# analog-frontend.net
KiCad netlist of a schematic drawn in EAGLE
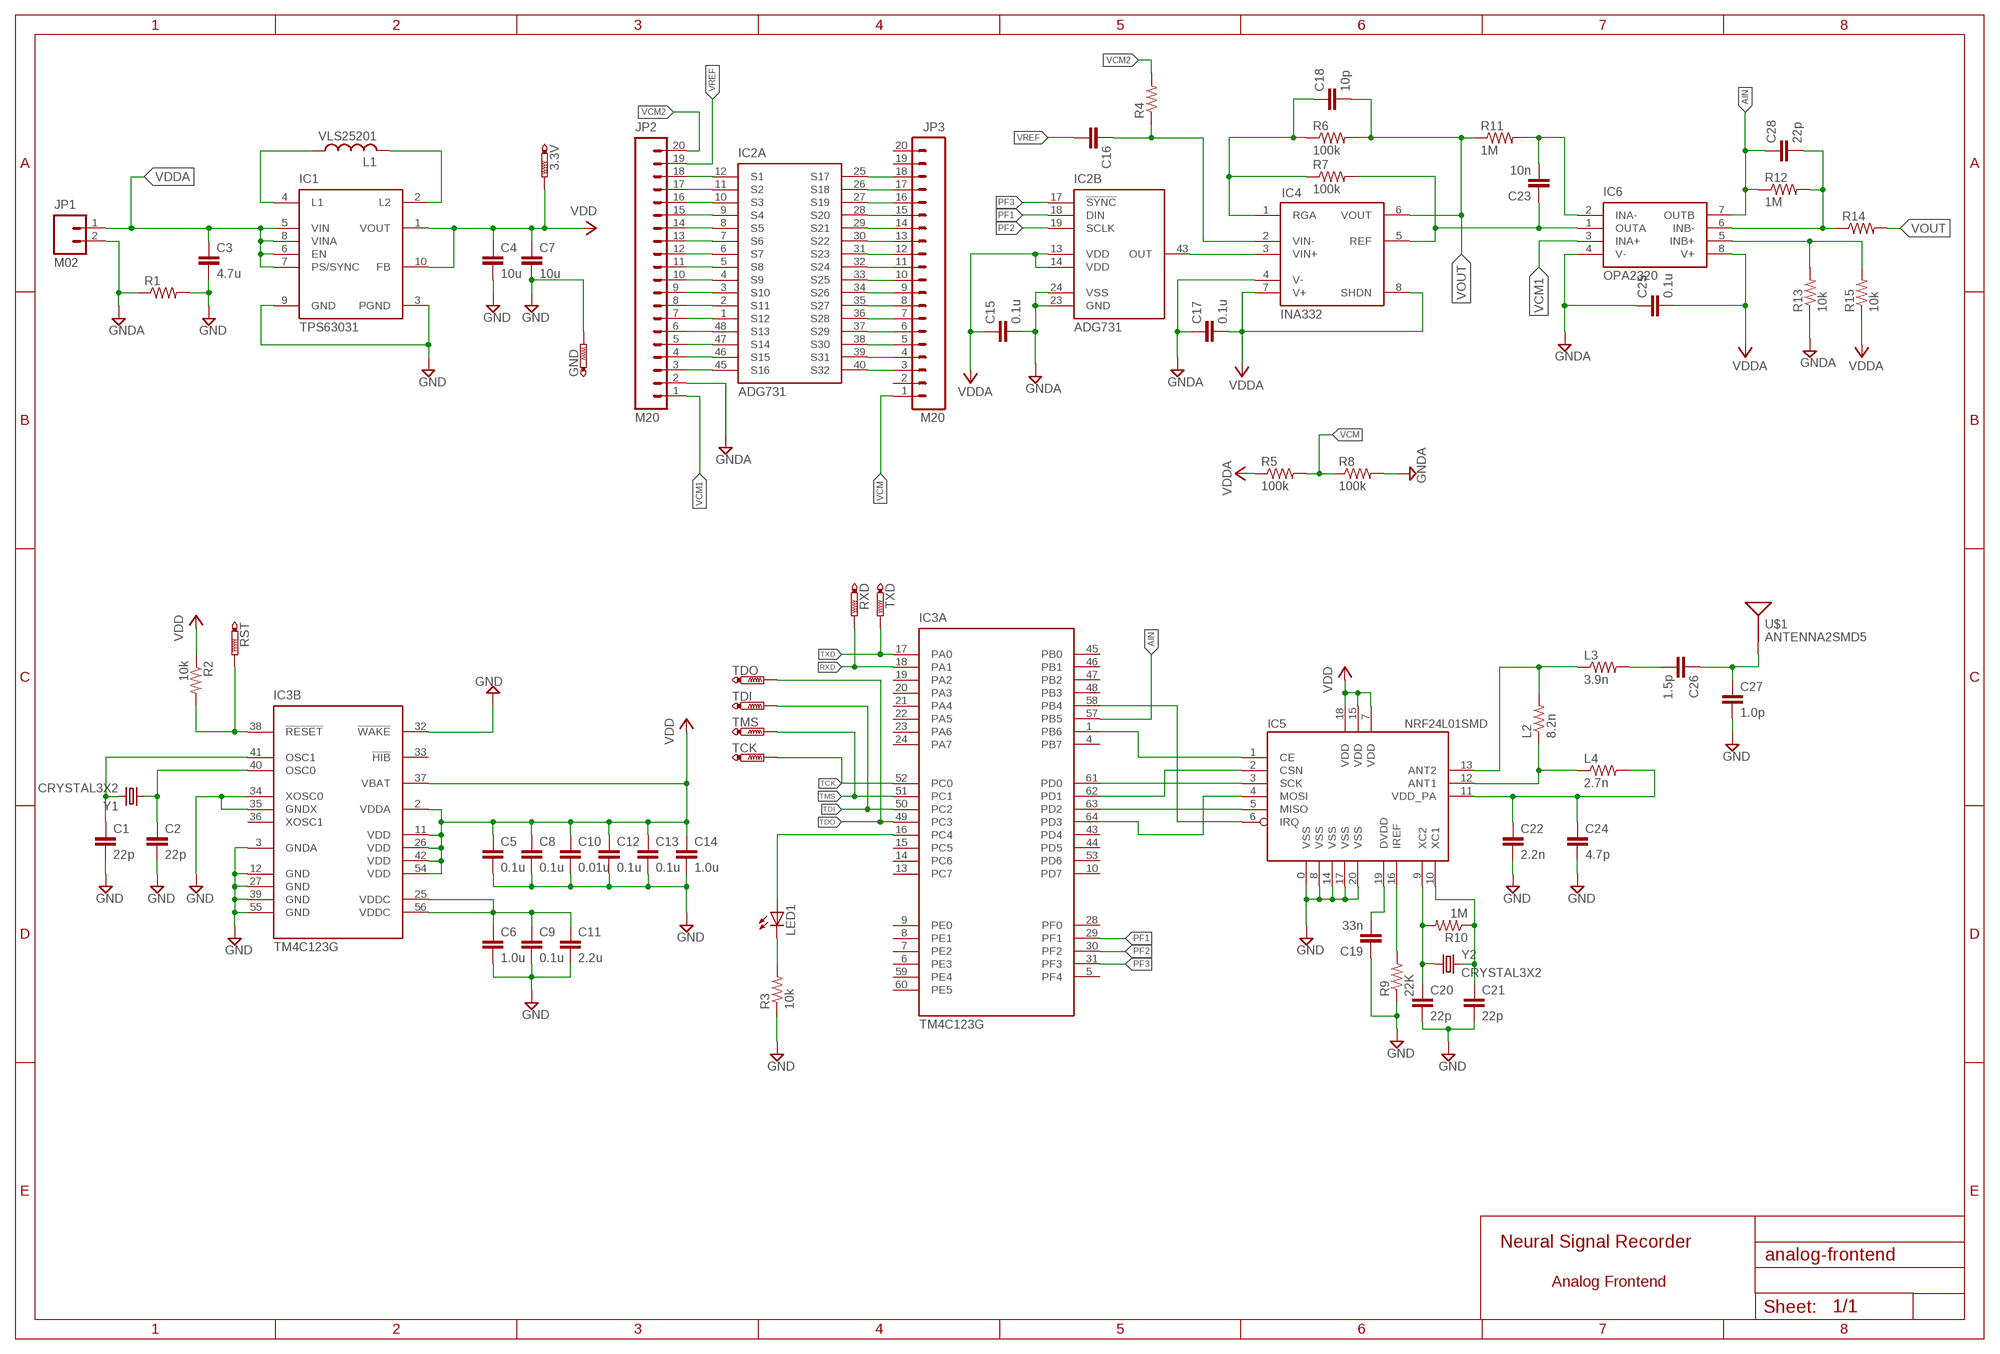
[diagram p0: schematic, sheet 1]

(export (version "E")
  (design (tool "Eeschema 10.0.6"))
  (components
    (comp (ref "3.3V")
      (value "PTR1B1,27")
      (footprint "eagle-import:B1,27")
      (libsource (lib "eagle-import") (part "PTR1B1,27"))
    )
    (comp (ref "C1")
      (value "22p")
      (footprint "eagle-import:C0402")
      (libsource (lib "eagle-import") (part "C-EUC0402"))
    )
    (comp (ref "C2")
      (value "22p")
      (footprint "eagle-import:C0402")
      (libsource (lib "eagle-import") (part "C-EUC0402"))
    )
    (comp (ref "C3")
      (value "4.7u")
      (footprint "eagle-import:C0402")
      (libsource (lib "eagle-import") (part "C-EUC0402"))
    )
    (comp (ref "C4")
      (value "10u")
      (footprint "eagle-import:C0402")
      (libsource (lib "eagle-import") (part "C-EUC0402"))
    )
    (comp (ref "C5")
      (value "0.1u")
      (footprint "eagle-import:C0402")
      (libsource (lib "eagle-import") (part "C-EUC0402"))
    )
    (comp (ref "C6")
      (value "1.0u")
      (footprint "eagle-import:C0402")
      (libsource (lib "eagle-import") (part "C-EUC0402"))
    )
    (comp (ref "C7")
      (value "10u")
      (footprint "eagle-import:C0402")
      (libsource (lib "eagle-import") (part "C-EUC0402"))
    )
    (comp (ref "C8")
      (value "0.1u")
      (footprint "eagle-import:C0402")
      (libsource (lib "eagle-import") (part "C-EUC0402"))
    )
    (comp (ref "C9")
      (value "0.1u")
      (footprint "eagle-import:C0402")
      (libsource (lib "eagle-import") (part "C-EUC0402"))
    )
    (comp (ref "C10")
      (value "0.01u")
      (footprint "eagle-import:C0402")
      (libsource (lib "eagle-import") (part "C-EUC0402"))
    )
    (comp (ref "C11")
      (value "2.2u")
      (footprint "eagle-import:C0402")
      (libsource (lib "eagle-import") (part "C-EUC0402"))
    )
    (comp (ref "C12")
      (value "0.1u")
      (footprint "eagle-import:C0402")
      (libsource (lib "eagle-import") (part "C-EUC0402"))
    )
    (comp (ref "C13")
      (value "0.1u")
      (footprint "eagle-import:C0402")
      (libsource (lib "eagle-import") (part "C-EUC0402"))
    )
    (comp (ref "C14")
      (value "1.0u")
      (footprint "eagle-import:C0402")
      (libsource (lib "eagle-import") (part "C-EUC0402"))
    )
    (comp (ref "C15")
      (value "0.1u")
      (footprint "eagle-import:C0402")
      (libsource (lib "eagle-import") (part "C-EUC0402"))
    )
    (comp (ref "C16")
      (value "C-EUC0402")
      (footprint "eagle-import:C0402")
      (libsource (lib "eagle-import") (part "C-EUC0402"))
    )
    (comp (ref "C17")
      (value "0.1u")
      (footprint "eagle-import:C0402")
      (libsource (lib "eagle-import") (part "C-EUC0402"))
    )
    (comp (ref "C18")
      (value "10p")
      (footprint "eagle-import:C0402")
      (libsource (lib "eagle-import") (part "C-EUC0402"))
    )
    (comp (ref "C19")
      (value "33n")
      (footprint "eagle-import:C0402")
      (libsource (lib "eagle-import") (part "C-EUC0402"))
    )
    (comp (ref "C20")
      (value "22p")
      (footprint "eagle-import:C0402")
      (libsource (lib "eagle-import") (part "C-EUC0402"))
    )
    (comp (ref "C21")
      (value "22p")
      (footprint "eagle-import:C0402")
      (libsource (lib "eagle-import") (part "C-EUC0402"))
    )
    (comp (ref "C22")
      (value "2.2n")
      (footprint "eagle-import:C0402")
      (libsource (lib "eagle-import") (part "C-EUC0402"))
    )
    (comp (ref "C23")
      (value "10n")
      (footprint "eagle-import:C0402")
      (libsource (lib "eagle-import") (part "C-EUC0402"))
    )
    (comp (ref "C24")
      (value "4.7p")
      (footprint "eagle-import:C0402")
      (libsource (lib "eagle-import") (part "C-EUC0402"))
    )
    (comp (ref "C25")
      (value "0.1u")
      (footprint "eagle-import:C0402")
      (libsource (lib "eagle-import") (part "C-EUC0402"))
    )
    (comp (ref "C26")
      (value "1.5p")
      (footprint "eagle-import:C0402")
      (libsource (lib "eagle-import") (part "C-EUC0402"))
    )
    (comp (ref "C27")
      (value "1.0p")
      (footprint "eagle-import:C0402")
      (libsource (lib "eagle-import") (part "C-EUC0402"))
    )
    (comp (ref "C28")
      (value "22p")
      (footprint "eagle-import:C0402")
      (libsource (lib "eagle-import") (part "C-EUC0402"))
    )
    (comp (ref "GND")
      (value "PTR1B1,27")
      (footprint "eagle-import:B1,27")
      (libsource (lib "eagle-import") (part "PTR1B1,27"))
    )
    (comp (ref "IC1")
      (value "TPS63031")
      (footprint "eagle-import:S-PDSO-N10")
      (libsource (lib "eagle-import") (part "TPS63031"))
    )
    (comp (ref "IC2")
      (value "ADG731")
      (footprint "eagle-import:LFCSP48")
      (libsource (lib "eagle-import") (part "ADG731"))
    )
    (comp (ref "IC3")
      (value "TM4C123G")
      (footprint "eagle-import:LQFP64")
      (libsource (lib "eagle-import") (part "TM4C123G"))
    )
    (comp (ref "IC4")
      (value "INA332")
      (footprint "eagle-import:DGK_S-PDSO-G8")
      (libsource (lib "eagle-import") (part "INA332"))
    )
    (comp (ref "IC5")
      (value "NRF24L01SMD")
      (footprint "eagle-import:QFN20")
      (libsource (lib "eagle-import") (part "NRF24L01SMD"))
    )
    (comp (ref "IC6")
      (value "OPA2320")
      (footprint "eagle-import:MSOP08")
      (libsource (lib "eagle-import") (part "OPA2320"))
    )
    (comp (ref "JP1")
      (value "M02")
      (footprint "eagle-import:1X02")
      (libsource (lib "eagle-import") (part "M02"))
    )
    (comp (ref "JP2")
      (value "M20")
      (footprint "eagle-import:1X20")
      (libsource (lib "eagle-import") (part "M20"))
    )
    (comp (ref "JP3")
      (value "M20")
      (footprint "eagle-import:1X20")
      (libsource (lib "eagle-import") (part "M20"))
    )
    (comp (ref "L1")
      (value "VLS25201")
      (footprint "eagle-import:L1008")
      (libsource (lib "eagle-import") (part "VLS25201"))
    )
    (comp (ref "L2")
      (value "8.2n")
      (footprint "eagle-import:R0402")
      (libsource (lib "eagle-import") (part "R-US_R0402"))
    )
    (comp (ref "L3")
      (value "3.9n")
      (footprint "eagle-import:R0402")
      (libsource (lib "eagle-import") (part "R-US_R0402"))
    )
    (comp (ref "L4")
      (value "2.7n")
      (footprint "eagle-import:R0402")
      (libsource (lib "eagle-import") (part "R-US_R0402"))
    )
    (comp (ref "LED1")
      (value "LED0402")
      (footprint "eagle-import:0402")
      (libsource (lib "eagle-import") (part "LED0402"))
    )
    (comp (ref "R1")
      (value "R-US_R0201")
      (footprint "eagle-import:R0201")
      (libsource (lib "eagle-import") (part "R-US_R0201"))
    )
    (comp (ref "R2")
      (value "10k")
      (footprint "eagle-import:R0402")
      (libsource (lib "eagle-import") (part "R-US_R0402"))
    )
    (comp (ref "R3")
      (value "10k")
      (footprint "eagle-import:R0402")
      (libsource (lib "eagle-import") (part "R-US_R0402"))
    )
    (comp (ref "R4")
      (value "R-US_R0402")
      (footprint "eagle-import:R0402")
      (libsource (lib "eagle-import") (part "R-US_R0402"))
    )
    (comp (ref "R5")
      (value "100k")
      (footprint "eagle-import:R0402")
      (libsource (lib "eagle-import") (part "R-US_R0402"))
    )
    (comp (ref "R6")
      (value "100k")
      (footprint "eagle-import:R0402")
      (libsource (lib "eagle-import") (part "R-US_R0402"))
    )
    (comp (ref "R7")
      (value "100k")
      (footprint "eagle-import:R0402")
      (libsource (lib "eagle-import") (part "R-US_R0402"))
    )
    (comp (ref "R8")
      (value "100k")
      (footprint "eagle-import:R0402")
      (libsource (lib "eagle-import") (part "R-US_R0402"))
    )
    (comp (ref "R9")
      (value "22K")
      (footprint "eagle-import:R0402")
      (libsource (lib "eagle-import") (part "R-US_R0402"))
    )
    (comp (ref "R10")
      (value "1M")
      (footprint "eagle-import:R0402")
      (libsource (lib "eagle-import") (part "R-US_R0402"))
    )
    (comp (ref "R11")
      (value "1M")
      (footprint "eagle-import:R0402")
      (libsource (lib "eagle-import") (part "R-US_R0402"))
    )
    (comp (ref "R12")
      (value "1M")
      (footprint "eagle-import:R0402")
      (libsource (lib "eagle-import") (part "R-US_R0402"))
    )
    (comp (ref "R13")
      (value "10k")
      (footprint "eagle-import:R0402")
      (libsource (lib "eagle-import") (part "R-US_R0402"))
    )
    (comp (ref "R14")
      (value "R-US_R0402")
      (footprint "eagle-import:R0402")
      (libsource (lib "eagle-import") (part "R-US_R0402"))
    )
    (comp (ref "R15")
      (value "10k")
      (footprint "eagle-import:R0402")
      (libsource (lib "eagle-import") (part "R-US_R0402"))
    )
    (comp (ref "RST")
      (value "PTR1B1,27")
      (footprint "eagle-import:B1,27")
      (libsource (lib "eagle-import") (part "PTR1B1,27"))
    )
    (comp (ref "RXD")
      (value "PTR1B1,27")
      (footprint "eagle-import:B1,27")
      (libsource (lib "eagle-import") (part "PTR1B1,27"))
    )
    (comp (ref "TCK")
      (value "PTR1B1,27")
      (footprint "eagle-import:B1,27")
      (libsource (lib "eagle-import") (part "PTR1B1,27"))
    )
    (comp (ref "TDI")
      (value "PTR1B1,27")
      (footprint "eagle-import:B1,27")
      (libsource (lib "eagle-import") (part "PTR1B1,27"))
    )
    (comp (ref "TDO")
      (value "PTR1B1,27")
      (footprint "eagle-import:B1,27")
      (libsource (lib "eagle-import") (part "PTR1B1,27"))
    )
    (comp (ref "TMS")
      (value "PTR1B1,27")
      (footprint "eagle-import:B1,27")
      (libsource (lib "eagle-import") (part "PTR1B1,27"))
    )
    (comp (ref "TXD")
      (value "PTR1B1,27")
      (footprint "eagle-import:B1,27")
      (libsource (lib "eagle-import") (part "PTR1B1,27"))
    )
    (comp (ref "U$1")
      (value "ANTENNA2SMD5")
      (footprint "eagle-import:ANTENNA-CHIP5")
      (libsource (lib "eagle-import") (part "ANTENNA2SMD5"))
    )
    (comp (ref "Y1")
      (value "CRYSTAL3X2")
      (footprint "eagle-import:SMDCRYSTAL3X2")
      (libsource (lib "eagle-import") (part "CRYSTAL3X2"))
    )
    (comp (ref "Y2")
      (value "CRYSTAL3X2")
      (footprint "eagle-import:SMDCRYSTAL3X2")
      (libsource (lib "eagle-import") (part "CRYSTAL3X2"))
    )
  )
  (nets
    (net (code "1") (name "AIN") (class "Default")
      (node (ref "C28") (pin "1") (pinfunction "1_1") (pintype "passive"))
      (node (ref "IC3") (pin "57") (pinfunction "PB5_57") (pintype "bidirectional"))
      (node (ref "IC6") (pin "7") (pinfunction "OUTB_7") (pintype "output"))
      (node (ref "R12") (pin "1") (pinfunction "1_1") (pintype "passive"))
    )
    (net (code "2") (name "GND") (class "Default")
      (node (ref "C1") (pin "2") (pinfunction "2_2") (pintype "passive"))
      (node (ref "C10") (pin "2") (pinfunction "2_2") (pintype "passive"))
      (node (ref "C11") (pin "2") (pinfunction "2_2") (pintype "passive"))
      (node (ref "C12") (pin "2") (pinfunction "2_2") (pintype "passive"))
      (node (ref "C13") (pin "2") (pinfunction "2_2") (pintype "passive"))
      (node (ref "C14") (pin "2") (pinfunction "2_2") (pintype "passive"))
      (node (ref "C19") (pin "1") (pinfunction "1_1") (pintype "passive"))
      (node (ref "C2") (pin "2") (pinfunction "2_2") (pintype "passive"))
      (node (ref "C20") (pin "2") (pinfunction "2_2") (pintype "passive"))
      (node (ref "C21") (pin "2") (pinfunction "2_2") (pintype "passive"))
      (node (ref "C22") (pin "2") (pinfunction "2_2") (pintype "passive"))
      (node (ref "C24") (pin "2") (pinfunction "2_2") (pintype "passive"))
      (node (ref "C27") (pin "2") (pinfunction "2_2") (pintype "passive"))
      (node (ref "C3") (pin "2") (pinfunction "2_2") (pintype "passive"))
      (node (ref "C4") (pin "2") (pinfunction "2_2") (pintype "passive"))
      (node (ref "C5") (pin "2") (pinfunction "2_2") (pintype "passive"))
      (node (ref "C6") (pin "2") (pinfunction "2_2") (pintype "passive"))
      (node (ref "C7") (pin "2") (pinfunction "2_2") (pintype "passive"))
      (node (ref "C8") (pin "2") (pinfunction "2_2") (pintype "passive"))
      (node (ref "C9") (pin "2") (pinfunction "2_2") (pintype "passive"))
      (node (ref "GND") (pin "TP") (pinfunction "TP_TP") (pintype "input"))
      (node (ref "IC1") (pin "3") (pinfunction "PGND_3") (pintype "power_in"))
      (node (ref "IC1") (pin "9") (pinfunction "GND_9") (pintype "power_in"))
      (node (ref "IC3") (pin "12") (pinfunction "GND_12") (pintype "power_in"))
      (node (ref "IC3") (pin "27") (pinfunction "GND_27") (pintype "power_in"))
      (node (ref "IC3") (pin "3") (pinfunction "GNDA_3") (pintype "power_in"))
      (node (ref "IC3") (pin "32") (pinfunction "~{WAKE}_32") (pintype "passive"))
      (node (ref "IC3") (pin "34") (pinfunction "XOSC0_34") (pintype "passive"))
      (node (ref "IC3") (pin "35") (pinfunction "GNDX_35") (pintype "passive"))
      (node (ref "IC3") (pin "39") (pinfunction "GND_39") (pintype "power_in"))
      (node (ref "IC3") (pin "55") (pinfunction "GND_55") (pintype "power_in"))
      (node (ref "IC5") (pin "0") (pinfunction "VSS_0") (pintype "power_in"))
      (node (ref "IC5") (pin "14") (pinfunction "VSS_14") (pintype "power_in"))
      (node (ref "IC5") (pin "17") (pinfunction "VSS_17") (pintype "power_in"))
      (node (ref "IC5") (pin "20") (pinfunction "VSS_20") (pintype "power_in"))
      (node (ref "IC5") (pin "8") (pinfunction "VSS_8") (pintype "power_in"))
      (node (ref "R1") (pin "2") (pinfunction "2_2") (pintype "passive"))
      (node (ref "R3") (pin "1") (pinfunction "1_1") (pintype "passive"))
      (node (ref "R9") (pin "1") (pinfunction "1_1") (pintype "passive"))
    )
    (net (code "3") (name "GNDA") (class "Default")
      (node (ref "C15") (pin "2") (pinfunction "2_2") (pintype "passive"))
      (node (ref "C17") (pin "1") (pinfunction "1_1") (pintype "passive"))
      (node (ref "C25") (pin "1") (pinfunction "1_1") (pintype "passive"))
      (node (ref "IC2") (pin "23") (pinfunction "GND_23") (pintype "bidirectional"))
      (node (ref "IC2") (pin "24") (pinfunction "VSS_24") (pintype "bidirectional"))
      (node (ref "IC4") (pin "4") (pinfunction "V-_4") (pintype "power_in"))
      (node (ref "IC6") (pin "4") (pinfunction "V-_4") (pintype "power_in"))
      (node (ref "JP1") (pin "2") (pinfunction "2_2") (pintype "passive"))
      (node (ref "JP2") (pin "2") (pinfunction "2_2") (pintype "passive"))
      (node (ref "R1") (pin "1") (pinfunction "1_1") (pintype "passive"))
      (node (ref "R13") (pin "1") (pinfunction "1_1") (pintype "passive"))
      (node (ref "R8") (pin "2") (pinfunction "2_2") (pintype "passive"))
    )
    (net (code "4") (name "Net-(C11-Pad1)") (class "Default")
      (node (ref "C11") (pin "1") (pinfunction "1_1") (pintype "passive"))
      (node (ref "C6") (pin "1") (pinfunction "1_1") (pintype "passive"))
      (node (ref "C9") (pin "1") (pinfunction "1_1") (pintype "passive"))
      (node (ref "IC3") (pin "25") (pinfunction "VDDC_25") (pintype "power_in"))
      (node (ref "IC3") (pin "56") (pinfunction "VDDC_56") (pintype "power_in"))
    )
    (net (code "5") (name "Net-(C26-Pad2)") (class "Default")
      (node (ref "C26") (pin "2") (pinfunction "2_2") (pintype "passive"))
      (node (ref "L3") (pin "2") (pinfunction "2_2") (pintype "passive"))
    )
    (net (code "6") (name "Net-(IC1-L1)") (class "Default")
      (node (ref "IC1") (pin "4") (pinfunction "L1_4") (pintype "passive"))
      (node (ref "L1") (pin "P$1") (pinfunction "1_P$1") (pintype "passive"))
    )
    (net (code "7") (name "Net-(IC1-L2)") (class "Default")
      (node (ref "IC1") (pin "2") (pinfunction "L2_2") (pintype "input"))
      (node (ref "L1") (pin "P$2") (pinfunction "2_P$2") (pintype "passive"))
    )
    (net (code "8") (name "Net-(IC2A-S1)") (class "Default")
      (node (ref "IC2") (pin "12") (pinfunction "S1_12") (pintype "bidirectional"))
      (node (ref "JP2") (pin "18") (pinfunction "18_18") (pintype "passive"))
    )
    (net (code "9") (name "Net-(IC2A-S2)") (class "Default")
      (node (ref "IC2") (pin "11") (pinfunction "S2_11") (pintype "bidirectional"))
      (node (ref "JP2") (pin "17") (pinfunction "17_17") (pintype "passive"))
    )
    (net (code "10") (name "Net-(IC2A-S3)") (class "Default")
      (node (ref "IC2") (pin "10") (pinfunction "S3_10") (pintype "bidirectional"))
      (node (ref "JP2") (pin "16") (pinfunction "16_16") (pintype "passive"))
    )
    (net (code "11") (name "Net-(IC2A-S4)") (class "Default")
      (node (ref "IC2") (pin "9") (pinfunction "S4_9") (pintype "bidirectional"))
      (node (ref "JP2") (pin "15") (pinfunction "15_15") (pintype "passive"))
    )
    (net (code "12") (name "Net-(IC2A-S5)") (class "Default")
      (node (ref "IC2") (pin "8") (pinfunction "S5_8") (pintype "bidirectional"))
      (node (ref "JP2") (pin "14") (pinfunction "14_14") (pintype "passive"))
    )
    (net (code "13") (name "Net-(IC2A-S6)") (class "Default")
      (node (ref "IC2") (pin "7") (pinfunction "S6_7") (pintype "bidirectional"))
      (node (ref "JP2") (pin "13") (pinfunction "13_13") (pintype "passive"))
    )
    (net (code "14") (name "Net-(IC2A-S7)") (class "Default")
      (node (ref "IC2") (pin "6") (pinfunction "S7_6") (pintype "bidirectional"))
      (node (ref "JP2") (pin "12") (pinfunction "12_12") (pintype "passive"))
    )
    (net (code "15") (name "Net-(IC2A-S8)") (class "Default")
      (node (ref "IC2") (pin "5") (pinfunction "S8_5") (pintype "bidirectional"))
      (node (ref "JP2") (pin "11") (pinfunction "11_11") (pintype "passive"))
    )
    (net (code "16") (name "Net-(IC2A-S9)") (class "Default")
      (node (ref "IC2") (pin "4") (pinfunction "S9_4") (pintype "bidirectional"))
      (node (ref "JP2") (pin "10") (pinfunction "10_10") (pintype "passive"))
    )
    (net (code "17") (name "Net-(IC2A-S10)") (class "Default")
      (node (ref "IC2") (pin "3") (pinfunction "S10_3") (pintype "bidirectional"))
      (node (ref "JP2") (pin "9") (pinfunction "9_9") (pintype "passive"))
    )
    (net (code "18") (name "Net-(IC2A-S11)") (class "Default")
      (node (ref "IC2") (pin "2") (pinfunction "S11_2") (pintype "bidirectional"))
      (node (ref "JP2") (pin "8") (pinfunction "8_8") (pintype "passive"))
    )
    (net (code "19") (name "Net-(IC2A-S12)") (class "Default")
      (node (ref "IC2") (pin "1") (pinfunction "S12_1") (pintype "bidirectional"))
      (node (ref "JP2") (pin "7") (pinfunction "7_7") (pintype "passive"))
    )
    (net (code "20") (name "Net-(IC2A-S13)") (class "Default")
      (node (ref "IC2") (pin "48") (pinfunction "S13_48") (pintype "bidirectional"))
      (node (ref "JP2") (pin "6") (pinfunction "6_6") (pintype "passive"))
    )
    (net (code "21") (name "Net-(IC2A-S14)") (class "Default")
      (node (ref "IC2") (pin "47") (pinfunction "S14_47") (pintype "bidirectional"))
      (node (ref "JP2") (pin "5") (pinfunction "5_5") (pintype "passive"))
    )
    (net (code "22") (name "Net-(IC2A-S15)") (class "Default")
      (node (ref "IC2") (pin "46") (pinfunction "S15_46") (pintype "bidirectional"))
      (node (ref "JP2") (pin "4") (pinfunction "4_4") (pintype "passive"))
    )
    (net (code "23") (name "Net-(IC2A-S16)") (class "Default")
      (node (ref "IC2") (pin "45") (pinfunction "S16_45") (pintype "bidirectional"))
      (node (ref "JP2") (pin "3") (pinfunction "3_3") (pintype "passive"))
    )
    (net (code "24") (name "Net-(IC2A-S17)") (class "Default")
      (node (ref "IC2") (pin "25") (pinfunction "S17_25") (pintype "bidirectional"))
      (node (ref "JP3") (pin "18") (pinfunction "18_18") (pintype "passive"))
    )
    (net (code "25") (name "Net-(IC2A-S18)") (class "Default")
      (node (ref "IC2") (pin "26") (pinfunction "S18_26") (pintype "bidirectional"))
      (node (ref "JP3") (pin "17") (pinfunction "17_17") (pintype "passive"))
    )
    (net (code "26") (name "Net-(IC2A-S19)") (class "Default")
      (node (ref "IC2") (pin "27") (pinfunction "S19_27") (pintype "bidirectional"))
      (node (ref "JP3") (pin "16") (pinfunction "16_16") (pintype "passive"))
    )
    (net (code "27") (name "Net-(IC2A-S20)") (class "Default")
      (node (ref "IC2") (pin "28") (pinfunction "S20_28") (pintype "bidirectional"))
      (node (ref "JP3") (pin "15") (pinfunction "15_15") (pintype "passive"))
    )
    (net (code "28") (name "Net-(IC2A-S21)") (class "Default")
      (node (ref "IC2") (pin "29") (pinfunction "S21_29") (pintype "bidirectional"))
      (node (ref "JP3") (pin "14") (pinfunction "14_14") (pintype "passive"))
    )
    (net (code "29") (name "Net-(IC2A-S22)") (class "Default")
      (node (ref "IC2") (pin "30") (pinfunction "S22_30") (pintype "bidirectional"))
      (node (ref "JP3") (pin "13") (pinfunction "13_13") (pintype "passive"))
    )
    (net (code "30") (name "Net-(IC2A-S23)") (class "Default")
      (node (ref "IC2") (pin "31") (pinfunction "S23_31") (pintype "bidirectional"))
      (node (ref "JP3") (pin "12") (pinfunction "12_12") (pintype "passive"))
    )
    (net (code "31") (name "Net-(IC2A-S24)") (class "Default")
      (node (ref "IC2") (pin "32") (pinfunction "S24_32") (pintype "bidirectional"))
      (node (ref "JP3") (pin "11") (pinfunction "11_11") (pintype "passive"))
    )
    (net (code "32") (name "Net-(IC2A-S25)") (class "Default")
      (node (ref "IC2") (pin "33") (pinfunction "S25_33") (pintype "bidirectional"))
      (node (ref "JP3") (pin "10") (pinfunction "10_10") (pintype "passive"))
    )
    (net (code "33") (name "Net-(IC2A-S26)") (class "Default")
      (node (ref "IC2") (pin "34") (pinfunction "S26_34") (pintype "bidirectional"))
      (node (ref "JP3") (pin "9") (pinfunction "9_9") (pintype "passive"))
    )
    (net (code "34") (name "Net-(IC2A-S27)") (class "Default")
      (node (ref "IC2") (pin "35") (pinfunction "S27_35") (pintype "bidirectional"))
      (node (ref "JP3") (pin "8") (pinfunction "8_8") (pintype "passive"))
    )
    (net (code "35") (name "Net-(IC2A-S28)") (class "Default")
      (node (ref "IC2") (pin "36") (pinfunction "S28_36") (pintype "bidirectional"))
      (node (ref "JP3") (pin "7") (pinfunction "7_7") (pintype "passive"))
    )
    (net (code "36") (name "Net-(IC2A-S29)") (class "Default")
      (node (ref "IC2") (pin "37") (pinfunction "S29_37") (pintype "bidirectional"))
      (node (ref "JP3") (pin "6") (pinfunction "6_6") (pintype "passive"))
    )
    (net (code "37") (name "Net-(IC2A-S30)") (class "Default")
      (node (ref "IC2") (pin "38") (pinfunction "S30_38") (pintype "bidirectional"))
      (node (ref "JP3") (pin "5") (pinfunction "5_5") (pintype "passive"))
    )
    (net (code "38") (name "Net-(IC2A-S31)") (class "Default")
      (node (ref "IC2") (pin "39") (pinfunction "S31_39") (pintype "bidirectional"))
      (node (ref "JP3") (pin "4") (pinfunction "4_4") (pintype "passive"))
    )
    (net (code "39") (name "Net-(IC2A-S32)") (class "Default")
      (node (ref "IC2") (pin "40") (pinfunction "S32_40") (pintype "bidirectional"))
      (node (ref "JP3") (pin "3") (pinfunction "3_3") (pintype "passive"))
    )
    (net (code "40") (name "Net-(IC2B-OUT)") (class "Default")
      (node (ref "IC2") (pin "43") (pinfunction "OUT_43") (pintype "output"))
      (node (ref "IC4") (pin "3") (pinfunction "VIN+_3") (pintype "input"))
    )
    (net (code "41") (name "Net-(IC3A-PB4)") (class "Default")
      (node (ref "IC3") (pin "58") (pinfunction "PB4_58") (pintype "bidirectional"))
      (node (ref "IC5") (pin "6") (pinfunction "IRQ_6") (pintype "output"))
    )
    (net (code "42") (name "Net-(IC3A-PB6)") (class "Default")
      (node (ref "IC3") (pin "1") (pinfunction "PB6_1") (pintype "bidirectional"))
      (node (ref "IC5") (pin "1") (pinfunction "CE_1") (pintype "input"))
    )
    (net (code "43") (name "Net-(IC3A-PC4)") (class "Default")
      (node (ref "IC3") (pin "16") (pinfunction "PC4_16") (pintype "bidirectional"))
      (node (ref "LED1") (pin "1") (pinfunction "A_1") (pintype "passive"))
    )
    (net (code "44") (name "Net-(IC3A-PD0)") (class "Default")
      (node (ref "IC3") (pin "61") (pinfunction "PD0_61") (pintype "bidirectional"))
      (node (ref "IC5") (pin "3") (pinfunction "SCK_3") (pintype "input"))
    )
    (net (code "45") (name "Net-(IC3A-PD1)") (class "Default")
      (node (ref "IC3") (pin "62") (pinfunction "PD1_62") (pintype "bidirectional"))
      (node (ref "IC5") (pin "2") (pinfunction "CSN_2") (pintype "input"))
    )
    (net (code "46") (name "Net-(IC3A-PD2)") (class "Default")
      (node (ref "IC3") (pin "63") (pinfunction "PD2_63") (pintype "bidirectional"))
      (node (ref "IC5") (pin "5") (pinfunction "MISO_5") (pintype "output"))
    )
    (net (code "47") (name "Net-(IC3A-PD3)") (class "Default")
      (node (ref "IC3") (pin "64") (pinfunction "PD3_64") (pintype "bidirectional"))
      (node (ref "IC5") (pin "4") (pinfunction "MOSI_4") (pintype "input"))
    )
    (net (code "48") (name "Net-(IC3B-OSC0)") (class "Default")
      (node (ref "C2") (pin "1") (pinfunction "1_1") (pintype "passive"))
      (node (ref "IC3") (pin "40") (pinfunction "OSC0_40") (pintype "passive"))
      (node (ref "Y1") (pin "1") (pinfunction "1_1") (pintype "passive"))
    )
    (net (code "49") (name "Net-(IC3B-OSC1)") (class "Default")
      (node (ref "C1") (pin "1") (pinfunction "1_1") (pintype "passive"))
      (node (ref "IC3") (pin "41") (pinfunction "OSC1_41") (pintype "passive"))
      (node (ref "Y1") (pin "3") (pinfunction "2_3") (pintype "passive"))
    )
    (net (code "50") (name "Net-(IC3B-~{RESET})") (class "Default")
      (node (ref "IC3") (pin "38") (pinfunction "~{RESET}_38") (pintype "passive"))
      (node (ref "R2") (pin "2") (pinfunction "2_2") (pintype "passive"))
      (node (ref "RST") (pin "TP") (pinfunction "TP_TP") (pintype "input"))
    )
    (net (code "51") (name "Net-(IC4-REF)") (class "Default")
      (node (ref "C23") (pin "1") (pinfunction "1_1") (pintype "passive"))
      (node (ref "IC4") (pin "5") (pinfunction "REF_5") (pintype "input"))
      (node (ref "IC6") (pin "1") (pinfunction "OUTA_1") (pintype "output"))
      (node (ref "R7") (pin "2") (pinfunction "2_2") (pintype "passive"))
    )
    (net (code "52") (name "Net-(IC4-RGA)") (class "Default")
      (node (ref "C18") (pin "1") (pinfunction "1_1") (pintype "passive"))
      (node (ref "IC4") (pin "1") (pinfunction "RGA_1") (pintype "passive"))
      (node (ref "R6") (pin "1") (pinfunction "1_1") (pintype "passive"))
      (node (ref "R7") (pin "1") (pinfunction "1_1") (pintype "passive"))
    )
    (net (code "53") (name "Net-(IC4-VIN-)") (class "Default")
      (node (ref "C16") (pin "1") (pinfunction "1_1") (pintype "passive"))
      (node (ref "IC4") (pin "2") (pinfunction "VIN-_2") (pintype "input"))
      (node (ref "R4") (pin "1") (pinfunction "1_1") (pintype "passive"))
    )
    (net (code "54") (name "Net-(IC5-ANT1)") (class "Default")
      (node (ref "IC5") (pin "12") (pinfunction "ANT1_12") (pintype "output"))
      (node (ref "L2") (pin "1") (pinfunction "1_1") (pintype "passive"))
      (node (ref "L4") (pin "1") (pinfunction "1_1") (pintype "passive"))
    )
    (net (code "55") (name "Net-(IC5-ANT2)") (class "Default")
      (node (ref "IC5") (pin "13") (pinfunction "ANT2_13") (pintype "output"))
      (node (ref "L2") (pin "2") (pinfunction "2_2") (pintype "passive"))
      (node (ref "L3") (pin "1") (pinfunction "1_1") (pintype "passive"))
    )
    (net (code "56") (name "Net-(IC5-DVDD)") (class "Default")
      (node (ref "C19") (pin "2") (pinfunction "2_2") (pintype "passive"))
      (node (ref "IC5") (pin "19") (pinfunction "DVDD_19") (pintype "power_in"))
    )
    (net (code "57") (name "Net-(IC5-IREF)") (class "Default")
      (node (ref "IC5") (pin "16") (pinfunction "IREF_16") (pintype "input"))
      (node (ref "R9") (pin "2") (pinfunction "2_2") (pintype "passive"))
    )
    (net (code "58") (name "Net-(IC5-VDD_PA)") (class "Default")
      (node (ref "C22") (pin "1") (pinfunction "1_1") (pintype "passive"))
      (node (ref "C24") (pin "1") (pinfunction "1_1") (pintype "passive"))
      (node (ref "IC5") (pin "11") (pinfunction "VDD_PA_11") (pintype "power_in"))
      (node (ref "L4") (pin "2") (pinfunction "2_2") (pintype "passive"))
    )
    (net (code "59") (name "Net-(IC5-XC1)") (class "Default")
      (node (ref "C21") (pin "1") (pinfunction "1_1") (pintype "passive"))
      (node (ref "IC5") (pin "10") (pinfunction "XC1_10") (pintype "input"))
      (node (ref "R10") (pin "1") (pinfunction "1_1") (pintype "passive"))
      (node (ref "Y2") (pin "3") (pinfunction "2_3") (pintype "passive"))
    )
    (net (code "60") (name "Net-(IC5-XC2)") (class "Default")
      (node (ref "C20") (pin "1") (pinfunction "1_1") (pintype "passive"))
      (node (ref "IC5") (pin "9") (pinfunction "XC2_9") (pintype "input"))
      (node (ref "R10") (pin "2") (pinfunction "2_2") (pintype "passive"))
      (node (ref "Y2") (pin "1") (pinfunction "1_1") (pintype "passive"))
    )
    (net (code "61") (name "Net-(IC6-INA-)") (class "Default")
      (node (ref "C23") (pin "2") (pinfunction "2_2") (pintype "passive"))
      (node (ref "IC6") (pin "2") (pinfunction "INA-_2") (pintype "input"))
      (node (ref "R11") (pin "2") (pinfunction "2_2") (pintype "passive"))
    )
    (net (code "62") (name "Net-(IC6-INB+)") (class "Default")
      (node (ref "IC6") (pin "5") (pinfunction "INB+_5") (pintype "input"))
      (node (ref "R13") (pin "2") (pinfunction "2_2") (pintype "passive"))
      (node (ref "R15") (pin "2") (pinfunction "2_2") (pintype "passive"))
    )
    (net (code "63") (name "Net-(IC6-INB-)") (class "Default")
      (node (ref "C28") (pin "2") (pinfunction "2_2") (pintype "passive"))
      (node (ref "IC6") (pin "6") (pinfunction "INB-_6") (pintype "input"))
      (node (ref "R12") (pin "2") (pinfunction "2_2") (pintype "passive"))
      (node (ref "R14") (pin "1") (pinfunction "1_1") (pintype "passive"))
    )
    (net (code "64") (name "Net-(LED1-C)") (class "Default")
      (node (ref "LED1") (pin "2") (pinfunction "C_2") (pintype "passive"))
      (node (ref "R3") (pin "2") (pinfunction "2_2") (pintype "passive"))
    )
    (net (code "65") (name "Net-(U$1-SIGNAL)") (class "Default")
      (node (ref "C26") (pin "1") (pinfunction "1_1") (pintype "passive"))
      (node (ref "C27") (pin "1") (pinfunction "1_1") (pintype "passive"))
      (node (ref "U$1") (pin "FEED") (pinfunction "SIGNAL_FEED") (pintype "bidirectional"))
    )
    (net (code "66") (name "PF1") (class "Default")
      (node (ref "IC2") (pin "18") (pinfunction "DIN_18") (pintype "input"))
      (node (ref "IC3") (pin "29") (pinfunction "PF1_29") (pintype "bidirectional"))
    )
    (net (code "67") (name "PF2") (class "Default")
      (node (ref "IC2") (pin "19") (pinfunction "SCLK_19") (pintype "input"))
      (node (ref "IC3") (pin "30") (pinfunction "PF2_30") (pintype "bidirectional"))
    )
    (net (code "68") (name "PF3") (class "Default")
      (node (ref "IC2") (pin "17") (pinfunction "~{SYNC}_17") (pintype "input"))
      (node (ref "IC3") (pin "31") (pinfunction "PF3_31") (pintype "bidirectional"))
    )
    (net (code "69") (name "RXD") (class "Default")
      (node (ref "IC3") (pin "18") (pinfunction "PA1_18") (pintype "bidirectional"))
      (node (ref "RXD") (pin "TP") (pinfunction "TP_TP") (pintype "input"))
    )
    (net (code "70") (name "TCK") (class "Default")
      (node (ref "IC3") (pin "52") (pinfunction "PC0_52") (pintype "bidirectional"))
      (node (ref "TCK") (pin "TP") (pinfunction "TP_TP") (pintype "input"))
    )
    (net (code "71") (name "TDI") (class "Default")
      (node (ref "IC3") (pin "50") (pinfunction "PC2_50") (pintype "bidirectional"))
      (node (ref "TDI") (pin "TP") (pinfunction "TP_TP") (pintype "input"))
    )
    (net (code "72") (name "TDO") (class "Default")
      (node (ref "IC3") (pin "49") (pinfunction "PC3_49") (pintype "bidirectional"))
      (node (ref "TDO") (pin "TP") (pinfunction "TP_TP") (pintype "input"))
    )
    (net (code "73") (name "TMS") (class "Default")
      (node (ref "IC3") (pin "51") (pinfunction "PC1_51") (pintype "bidirectional"))
      (node (ref "TMS") (pin "TP") (pinfunction "TP_TP") (pintype "input"))
    )
    (net (code "74") (name "TXD") (class "Default")
      (node (ref "IC3") (pin "17") (pinfunction "PA0_17") (pintype "bidirectional"))
      (node (ref "TXD") (pin "TP") (pinfunction "TP_TP") (pintype "input"))
    )
    (net (code "75") (name "VCM") (class "Default")
      (node (ref "JP3") (pin "1") (pinfunction "1_1") (pintype "passive"))
      (node (ref "R5") (pin "2") (pinfunction "2_2") (pintype "passive"))
      (node (ref "R8") (pin "1") (pinfunction "1_1") (pintype "passive"))
    )
    (net (code "76") (name "VCM1") (class "Default")
      (node (ref "IC6") (pin "3") (pinfunction "INA+_3") (pintype "input"))
      (node (ref "JP2") (pin "1") (pinfunction "1_1") (pintype "passive"))
    )
    (net (code "77") (name "VCM2") (class "Default")
      (node (ref "JP2") (pin "20") (pinfunction "20_20") (pintype "passive"))
      (node (ref "R4") (pin "2") (pinfunction "2_2") (pintype "passive"))
    )
    (net (code "78") (name "VDD") (class "Default")
      (node (ref "3.3V") (pin "TP") (pinfunction "TP_TP") (pintype "input"))
      (node (ref "C10") (pin "1") (pinfunction "1_1") (pintype "passive"))
      (node (ref "C12") (pin "1") (pinfunction "1_1") (pintype "passive"))
      (node (ref "C13") (pin "1") (pinfunction "1_1") (pintype "passive"))
      (node (ref "C14") (pin "1") (pinfunction "1_1") (pintype "passive"))
      (node (ref "C4") (pin "1") (pinfunction "1_1") (pintype "passive"))
      (node (ref "C5") (pin "1") (pinfunction "1_1") (pintype "passive"))
      (node (ref "C7") (pin "1") (pinfunction "1_1") (pintype "passive"))
      (node (ref "C8") (pin "1") (pinfunction "1_1") (pintype "passive"))
      (node (ref "IC1") (pin "1") (pinfunction "VOUT_1") (pintype "output"))
      (node (ref "IC1") (pin "10") (pinfunction "FB_10") (pintype "input"))
      (node (ref "IC3") (pin "11") (pinfunction "VDD_11") (pintype "power_in"))
      (node (ref "IC3") (pin "2") (pinfunction "VDDA_2") (pintype "power_in"))
      (node (ref "IC3") (pin "26") (pinfunction "VDD_26") (pintype "power_in"))
      (node (ref "IC3") (pin "37") (pinfunction "VBAT_37") (pintype "power_in"))
      (node (ref "IC3") (pin "42") (pinfunction "VDD_42") (pintype "power_in"))
      (node (ref "IC3") (pin "54") (pinfunction "VDD_54") (pintype "power_in"))
      (node (ref "IC5") (pin "15") (pinfunction "VDD_15") (pintype "power_in"))
      (node (ref "IC5") (pin "18") (pinfunction "VDD_18") (pintype "power_in"))
      (node (ref "IC5") (pin "7") (pinfunction "VDD_7") (pintype "power_in"))
      (node (ref "R2") (pin "1") (pinfunction "1_1") (pintype "passive"))
    )
    (net (code "79") (name "VDDA") (class "Default")
      (node (ref "C15") (pin "1") (pinfunction "1_1") (pintype "passive"))
      (node (ref "C17") (pin "2") (pinfunction "2_2") (pintype "passive"))
      (node (ref "C25") (pin "2") (pinfunction "2_2") (pintype "passive"))
      (node (ref "C3") (pin "1") (pinfunction "1_1") (pintype "passive"))
      (node (ref "IC1") (pin "5") (pinfunction "VIN_5") (pintype "input"))
      (node (ref "IC1") (pin "6") (pinfunction "EN_6") (pintype "input"))
      (node (ref "IC1") (pin "7") (pinfunction "PS/SYNC_7") (pintype "input"))
      (node (ref "IC1") (pin "8") (pinfunction "VINA_8") (pintype "input"))
      (node (ref "IC2") (pin "13") (pinfunction "VDD_13") (pintype "bidirectional"))
      (node (ref "IC2") (pin "14") (pinfunction "VDD_14") (pintype "bidirectional"))
      (node (ref "IC4") (pin "7") (pinfunction "V+_7") (pintype "power_in"))
      (node (ref "IC4") (pin "8") (pinfunction "SHDN_8") (pintype "input"))
      (node (ref "IC6") (pin "8") (pinfunction "V+_8") (pintype "power_in"))
      (node (ref "JP1") (pin "1") (pinfunction "1_1") (pintype "passive"))
      (node (ref "R15") (pin "1") (pinfunction "1_1") (pintype "passive"))
      (node (ref "R5") (pin "1") (pinfunction "1_1") (pintype "passive"))
    )
    (net (code "80") (name "VOUT") (class "Default")
      (node (ref "C18") (pin "2") (pinfunction "2_2") (pintype "passive"))
      (node (ref "IC4") (pin "6") (pinfunction "VOUT_6") (pintype "output"))
      (node (ref "R11") (pin "1") (pinfunction "1_1") (pintype "passive"))
      (node (ref "R14") (pin "2") (pinfunction "2_2") (pintype "passive"))
      (node (ref "R6") (pin "2") (pinfunction "2_2") (pintype "passive"))
    )
    (net (code "81") (name "VREF") (class "Default")
      (node (ref "C16") (pin "2") (pinfunction "2_2") (pintype "passive"))
      (node (ref "JP2") (pin "19") (pinfunction "19_19") (pintype "passive"))
    )
    (net (code "82") (name "unconnected-(IC3A-PA2-Pad19)") (class "Default")
      (node (ref "IC3") (pin "19") (pinfunction "PA2_19") (pintype "bidirectional"))
    )
    (net (code "83") (name "unconnected-(IC3A-PA3-Pad20)") (class "Default")
      (node (ref "IC3") (pin "20") (pinfunction "PA3_20") (pintype "bidirectional"))
    )
    (net (code "84") (name "unconnected-(IC3A-PA4-Pad21)") (class "Default")
      (node (ref "IC3") (pin "21") (pinfunction "PA4_21") (pintype "bidirectional"))
    )
    (net (code "85") (name "unconnected-(IC3A-PA5-Pad22)") (class "Default")
      (node (ref "IC3") (pin "22") (pinfunction "PA5_22") (pintype "bidirectional"))
    )
    (net (code "86") (name "unconnected-(IC3A-PA6-Pad23)") (class "Default")
      (node (ref "IC3") (pin "23") (pinfunction "PA6_23") (pintype "bidirectional"))
    )
    (net (code "87") (name "unconnected-(IC3A-PA7-Pad24)") (class "Default")
      (node (ref "IC3") (pin "24") (pinfunction "PA7_24") (pintype "bidirectional"))
    )
    (net (code "88") (name "unconnected-(IC3A-PB0-Pad45)") (class "Default")
      (node (ref "IC3") (pin "45") (pinfunction "PB0_45") (pintype "bidirectional"))
    )
    (net (code "89") (name "unconnected-(IC3A-PB1-Pad46)") (class "Default")
      (node (ref "IC3") (pin "46") (pinfunction "PB1_46") (pintype "bidirectional"))
    )
    (net (code "90") (name "unconnected-(IC3A-PB2-Pad47)") (class "Default")
      (node (ref "IC3") (pin "47") (pinfunction "PB2_47") (pintype "bidirectional"))
    )
    (net (code "91") (name "unconnected-(IC3A-PB3-Pad48)") (class "Default")
      (node (ref "IC3") (pin "48") (pinfunction "PB3_48") (pintype "bidirectional"))
    )
    (net (code "92") (name "unconnected-(IC3A-PB7-Pad4)") (class "Default")
      (node (ref "IC3") (pin "4") (pinfunction "PB7_4") (pintype "bidirectional"))
    )
    (net (code "93") (name "unconnected-(IC3A-PC5-Pad15)") (class "Default")
      (node (ref "IC3") (pin "15") (pinfunction "PC5_15") (pintype "bidirectional"))
    )
    (net (code "94") (name "unconnected-(IC3A-PC6-Pad14)") (class "Default")
      (node (ref "IC3") (pin "14") (pinfunction "PC6_14") (pintype "bidirectional"))
    )
    (net (code "95") (name "unconnected-(IC3A-PC7-Pad13)") (class "Default")
      (node (ref "IC3") (pin "13") (pinfunction "PC7_13") (pintype "bidirectional"))
    )
    (net (code "96") (name "unconnected-(IC3A-PD4-Pad43)") (class "Default")
      (node (ref "IC3") (pin "43") (pinfunction "PD4_43") (pintype "bidirectional"))
    )
    (net (code "97") (name "unconnected-(IC3A-PD5-Pad44)") (class "Default")
      (node (ref "IC3") (pin "44") (pinfunction "PD5_44") (pintype "bidirectional"))
    )
    (net (code "98") (name "unconnected-(IC3A-PD6-Pad53)") (class "Default")
      (node (ref "IC3") (pin "53") (pinfunction "PD6_53") (pintype "bidirectional"))
    )
    (net (code "99") (name "unconnected-(IC3A-PD7-Pad10)") (class "Default")
      (node (ref "IC3") (pin "10") (pinfunction "PD7_10") (pintype "bidirectional"))
    )
    (net (code "100") (name "unconnected-(IC3A-PE0-Pad9)") (class "Default")
      (node (ref "IC3") (pin "9") (pinfunction "PE0_9") (pintype "bidirectional"))
    )
    (net (code "101") (name "unconnected-(IC3A-PE1-Pad8)") (class "Default")
      (node (ref "IC3") (pin "8") (pinfunction "PE1_8") (pintype "bidirectional"))
    )
    (net (code "102") (name "unconnected-(IC3A-PE2-Pad7)") (class "Default")
      (node (ref "IC3") (pin "7") (pinfunction "PE2_7") (pintype "bidirectional"))
    )
    (net (code "103") (name "unconnected-(IC3A-PE3-Pad6)") (class "Default")
      (node (ref "IC3") (pin "6") (pinfunction "PE3_6") (pintype "bidirectional"))
    )
    (net (code "104") (name "unconnected-(IC3A-PE4-Pad59)") (class "Default")
      (node (ref "IC3") (pin "59") (pinfunction "PE4_59") (pintype "bidirectional"))
    )
    (net (code "105") (name "unconnected-(IC3A-PE5-Pad60)") (class "Default")
      (node (ref "IC3") (pin "60") (pinfunction "PE5_60") (pintype "bidirectional"))
    )
    (net (code "106") (name "unconnected-(IC3A-PF0-Pad28)") (class "Default")
      (node (ref "IC3") (pin "28") (pinfunction "PF0_28") (pintype "bidirectional"))
    )
    (net (code "107") (name "unconnected-(IC3A-PF4-Pad5)") (class "Default")
      (node (ref "IC3") (pin "5") (pinfunction "PF4_5") (pintype "bidirectional"))
    )
    (net (code "108") (name "unconnected-(IC3B-XOSC1-Pad36)") (class "Default")
      (node (ref "IC3") (pin "36") (pinfunction "XOSC1_36") (pintype "passive"))
    )
    (net (code "109") (name "unconnected-(IC3B-~{HIB}-Pad33)") (class "Default")
      (node (ref "IC3") (pin "33") (pinfunction "~{HIB}_33") (pintype "passive"))
    )
    (net (code "110") (name "unconnected-(JP3-Pad2)") (class "Default")
      (node (ref "JP3") (pin "2") (pinfunction "2_2") (pintype "passive"))
    )
    (net (code "111") (name "unconnected-(JP3-Pad19)") (class "Default")
      (node (ref "JP3") (pin "19") (pinfunction "19_19") (pintype "passive"))
    )
    (net (code "112") (name "unconnected-(JP3-Pad20)") (class "Default")
      (node (ref "JP3") (pin "20") (pinfunction "20_20") (pintype "passive"))
    )
  )
)
